# esquematico.net
KiCad netlist of a schematic drawn in EAGLE
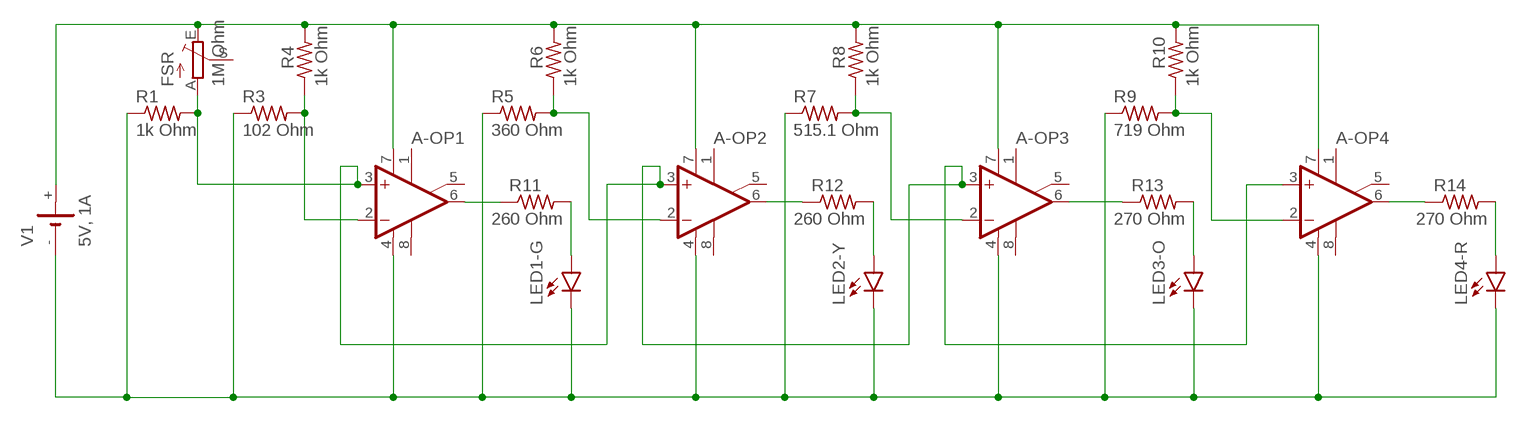
[diagram p0: schematic, sheet 1]

(export (version "E")
  (design (tool "Eeschema 10.0.6"))
  (components
    (comp (ref "A-OP1")
      (value "UA741P")
      (footprint "eagle-import:DIL08")
      (libsource (lib "eagle-import") (part "741PUA"))
    )
    (comp (ref "A-OP2")
      (value "UA741P")
      (footprint "eagle-import:DIL08")
      (libsource (lib "eagle-import") (part "741PUA"))
    )
    (comp (ref "A-OP3")
      (value "UA741P")
      (footprint "eagle-import:DIL08")
      (libsource (lib "eagle-import") (part "741PUA"))
    )
    (comp (ref "A-OP4")
      (value "UA741P")
      (footprint "eagle-import:DIL08")
      (libsource (lib "eagle-import") (part "741PUA"))
    )
    (comp (ref "FSR")
      (value "1M Ohm")
      (footprint "eagle-import:CIP20C-4MM")
      (libsource (lib "eagle-import") (part "TRIM_EU-CIP20C-4MM"))
    )
    (comp (ref "LED1-G")
      (value "TLLR4400")
      (footprint "eagle-import:LED3MM")
      (fields (field (name "MF") "VISHAY SEMICONDUCTOR"))
      (libsource (lib "eagle-import") (part "TLLR4400"))
    )
    (comp (ref "LED2-Y")
      (value "TLLR4400")
      (footprint "eagle-import:LED3MM")
      (fields (field (name "MF") "VISHAY SEMICONDUCTOR"))
      (libsource (lib "eagle-import") (part "TLLR4400"))
    )
    (comp (ref "LED3-O")
      (value "TLLR4400")
      (footprint "eagle-import:LED3MM")
      (fields (field (name "MF") "VISHAY SEMICONDUCTOR"))
      (libsource (lib "eagle-import") (part "TLLR4400"))
    )
    (comp (ref "LED4-R")
      (value "TLLR4400")
      (footprint "eagle-import:LED3MM")
      (fields (field (name "MF") "VISHAY SEMICONDUCTOR"))
      (libsource (lib "eagle-import") (part "TLLR4400"))
    )
    (comp (ref "R1")
      (value "1k Ohm")
      (footprint "eagle-import:0204_5")
      (libsource (lib "eagle-import") (part "R-US_0204/5"))
    )
    (comp (ref "R3")
      (value "102 Ohm")
      (footprint "eagle-import:0204_5")
      (libsource (lib "eagle-import") (part "R-US_0204/5"))
    )
    (comp (ref "R4")
      (value "1k Ohm")
      (footprint "eagle-import:0204_5")
      (libsource (lib "eagle-import") (part "R-US_0204/5"))
    )
    (comp (ref "R5")
      (value "360 Ohm")
      (footprint "eagle-import:0204_5")
      (libsource (lib "eagle-import") (part "R-US_0204/5"))
    )
    (comp (ref "R6")
      (value "1k Ohm")
      (footprint "eagle-import:0204_5")
      (libsource (lib "eagle-import") (part "R-US_0204/5"))
    )
    (comp (ref "R7")
      (value "515.1 Ohm")
      (footprint "eagle-import:0204_5")
      (libsource (lib "eagle-import") (part "R-US_0204/5"))
    )
    (comp (ref "R8")
      (value "1k Ohm")
      (footprint "eagle-import:0204_5")
      (libsource (lib "eagle-import") (part "R-US_0204/5"))
    )
    (comp (ref "R9")
      (value "719 Ohm")
      (footprint "eagle-import:0204_5")
      (libsource (lib "eagle-import") (part "R-US_0204/5"))
    )
    (comp (ref "R10")
      (value "1k Ohm")
      (footprint "eagle-import:0204_5")
      (libsource (lib "eagle-import") (part "R-US_0204/5"))
    )
    (comp (ref "R11")
      (value "260 Ohm")
      (footprint "eagle-import:0204_5")
      (libsource (lib "eagle-import") (part "R-US_0204/5"))
    )
    (comp (ref "R12")
      (value "260 Ohm")
      (footprint "eagle-import:0204_5")
      (libsource (lib "eagle-import") (part "R-US_0204/5"))
    )
    (comp (ref "R13")
      (value "270 Ohm")
      (footprint "eagle-import:0204_5")
      (libsource (lib "eagle-import") (part "R-US_0204/5"))
    )
    (comp (ref "R14")
      (value "270 Ohm")
      (footprint "eagle-import:0204_5")
      (libsource (lib "eagle-import") (part "R-US_0204/5"))
    )
    (comp (ref "V1")
      (value "5V, 1A")
      (footprint "eagle-import:CH291-1220LF")
      (libsource (lib "eagle-import") (part "CH291-1220LF"))
    )
  )
  (nets
    (net (code "1") (name "Net-(A-OP1-+IN)") (class "Default")
      (node (ref "A-OP1") (pin "3") (pinfunction "+IN_3") (pintype "input"))
      (node (ref "A-OP2") (pin "3") (pinfunction "+IN_3") (pintype "input"))
      (node (ref "A-OP3") (pin "3") (pinfunction "+IN_3") (pintype "input"))
      (node (ref "A-OP4") (pin "3") (pinfunction "+IN_3") (pintype "input"))
      (node (ref "FSR") (pin "A") (pinfunction "A_A") (pintype "passive"))
      (node (ref "R1") (pin "2") (pinfunction "2_2") (pintype "passive"))
    )
    (net (code "2") (name "Net-(A-OP1--IN)") (class "Default")
      (node (ref "A-OP1") (pin "2") (pinfunction "-IN_2") (pintype "input"))
      (node (ref "R3") (pin "2") (pinfunction "2_2") (pintype "passive"))
      (node (ref "R4") (pin "1") (pinfunction "1_1") (pintype "passive"))
    )
    (net (code "3") (name "Net-(A-OP1-OUT)") (class "Default")
      (node (ref "A-OP1") (pin "6") (pinfunction "OUT_6") (pintype "output"))
      (node (ref "R11") (pin "1") (pinfunction "1_1") (pintype "passive"))
    )
    (net (code "4") (name "Net-(A-OP1-V+)") (class "Default")
      (node (ref "A-OP1") (pin "7") (pinfunction "V+_7") (pintype "power_in"))
      (node (ref "A-OP2") (pin "7") (pinfunction "V+_7") (pintype "power_in"))
      (node (ref "A-OP3") (pin "7") (pinfunction "V+_7") (pintype "power_in"))
      (node (ref "A-OP4") (pin "7") (pinfunction "V+_7") (pintype "power_in"))
      (node (ref "FSR") (pin "E") (pinfunction "E_E") (pintype "passive"))
      (node (ref "R10") (pin "2") (pinfunction "2_2") (pintype "passive"))
      (node (ref "R4") (pin "2") (pinfunction "2_2") (pintype "passive"))
      (node (ref "R6") (pin "2") (pinfunction "2_2") (pintype "passive"))
      (node (ref "R8") (pin "2") (pinfunction "2_2") (pintype "passive"))
      (node (ref "V1") (pin "+") (pinfunction "+_+") (pintype "passive"))
    )
    (net (code "5") (name "Net-(A-OP1-V-)") (class "Default")
      (node (ref "A-OP1") (pin "4") (pinfunction "V-_4") (pintype "power_in"))
      (node (ref "A-OP2") (pin "4") (pinfunction "V-_4") (pintype "power_in"))
      (node (ref "A-OP3") (pin "4") (pinfunction "V-_4") (pintype "power_in"))
      (node (ref "A-OP4") (pin "4") (pinfunction "V-_4") (pintype "power_in"))
      (node (ref "LED1-G") (pin "K") (pinfunction "C_K") (pintype "passive"))
      (node (ref "LED2-Y") (pin "K") (pinfunction "C_K") (pintype "passive"))
      (node (ref "LED3-O") (pin "K") (pinfunction "C_K") (pintype "passive"))
      (node (ref "LED4-R") (pin "K") (pinfunction "C_K") (pintype "passive"))
      (node (ref "R1") (pin "1") (pinfunction "1_1") (pintype "passive"))
      (node (ref "R3") (pin "1") (pinfunction "1_1") (pintype "passive"))
      (node (ref "R5") (pin "1") (pinfunction "1_1") (pintype "passive"))
      (node (ref "R7") (pin "1") (pinfunction "1_1") (pintype "passive"))
      (node (ref "R9") (pin "1") (pinfunction "1_1") (pintype "passive"))
      (node (ref "V1") (pin "-") (pinfunction "-_-") (pintype "passive"))
    )
    (net (code "6") (name "Net-(A-OP2--IN)") (class "Default")
      (node (ref "A-OP2") (pin "2") (pinfunction "-IN_2") (pintype "input"))
      (node (ref "R5") (pin "2") (pinfunction "2_2") (pintype "passive"))
      (node (ref "R6") (pin "1") (pinfunction "1_1") (pintype "passive"))
    )
    (net (code "7") (name "Net-(A-OP2-OUT)") (class "Default")
      (node (ref "A-OP2") (pin "6") (pinfunction "OUT_6") (pintype "output"))
      (node (ref "R12") (pin "1") (pinfunction "1_1") (pintype "passive"))
    )
    (net (code "8") (name "Net-(A-OP3--IN)") (class "Default")
      (node (ref "A-OP3") (pin "2") (pinfunction "-IN_2") (pintype "input"))
      (node (ref "R7") (pin "2") (pinfunction "2_2") (pintype "passive"))
      (node (ref "R8") (pin "1") (pinfunction "1_1") (pintype "passive"))
    )
    (net (code "9") (name "Net-(A-OP3-OUT)") (class "Default")
      (node (ref "A-OP3") (pin "6") (pinfunction "OUT_6") (pintype "output"))
      (node (ref "R13") (pin "1") (pinfunction "1_1") (pintype "passive"))
    )
    (net (code "10") (name "Net-(A-OP4--IN)") (class "Default")
      (node (ref "A-OP4") (pin "2") (pinfunction "-IN_2") (pintype "input"))
      (node (ref "R10") (pin "1") (pinfunction "1_1") (pintype "passive"))
      (node (ref "R9") (pin "2") (pinfunction "2_2") (pintype "passive"))
    )
    (net (code "11") (name "Net-(A-OP4-OUT)") (class "Default")
      (node (ref "A-OP4") (pin "6") (pinfunction "OUT_6") (pintype "output"))
      (node (ref "R14") (pin "1") (pinfunction "1_1") (pintype "passive"))
    )
    (net (code "12") (name "Net-(LED1-G-PadA)") (class "Default")
      (node (ref "LED1-G") (pin "A") (pinfunction "A_A") (pintype "passive"))
      (node (ref "R11") (pin "2") (pinfunction "2_2") (pintype "passive"))
    )
    (net (code "13") (name "Net-(LED2-Y-PadA)") (class "Default")
      (node (ref "LED2-Y") (pin "A") (pinfunction "A_A") (pintype "passive"))
      (node (ref "R12") (pin "2") (pinfunction "2_2") (pintype "passive"))
    )
    (net (code "14") (name "Net-(LED3-O-PadA)") (class "Default")
      (node (ref "LED3-O") (pin "A") (pinfunction "A_A") (pintype "passive"))
      (node (ref "R13") (pin "2") (pinfunction "2_2") (pintype "passive"))
    )
    (net (code "15") (name "Net-(LED4-R-PadA)") (class "Default")
      (node (ref "LED4-R") (pin "A") (pinfunction "A_A") (pintype "passive"))
      (node (ref "R14") (pin "2") (pinfunction "2_2") (pintype "passive"))
    )
    (net (code "16") (name "unconnected-(A-OP1-ON1-Pad1)") (class "Default")
      (node (ref "A-OP1") (pin "1") (pinfunction "ON1_1") (pintype "passive"))
    )
    (net (code "17") (name "unconnected-(A-OP1-ON2-Pad5)") (class "Default")
      (node (ref "A-OP1") (pin "5") (pinfunction "ON2_5") (pintype "passive"))
    )
    (net (code "18") (name "unconnected-(A-OP1-OPT-Pad8)") (class "Default")
      (node (ref "A-OP1") (pin "8") (pinfunction "OPT_8") (pintype "passive"))
    )
    (net (code "19") (name "unconnected-(A-OP2-ON1-Pad1)") (class "Default")
      (node (ref "A-OP2") (pin "1") (pinfunction "ON1_1") (pintype "passive"))
    )
    (net (code "20") (name "unconnected-(A-OP2-ON2-Pad5)") (class "Default")
      (node (ref "A-OP2") (pin "5") (pinfunction "ON2_5") (pintype "passive"))
    )
    (net (code "21") (name "unconnected-(A-OP2-OPT-Pad8)") (class "Default")
      (node (ref "A-OP2") (pin "8") (pinfunction "OPT_8") (pintype "passive"))
    )
    (net (code "22") (name "unconnected-(A-OP3-ON1-Pad1)") (class "Default")
      (node (ref "A-OP3") (pin "1") (pinfunction "ON1_1") (pintype "passive"))
    )
    (net (code "23") (name "unconnected-(A-OP3-ON2-Pad5)") (class "Default")
      (node (ref "A-OP3") (pin "5") (pinfunction "ON2_5") (pintype "passive"))
    )
    (net (code "24") (name "unconnected-(A-OP3-OPT-Pad8)") (class "Default")
      (node (ref "A-OP3") (pin "8") (pinfunction "OPT_8") (pintype "passive"))
    )
    (net (code "25") (name "unconnected-(A-OP4-ON1-Pad1)") (class "Default")
      (node (ref "A-OP4") (pin "1") (pinfunction "ON1_1") (pintype "passive"))
    )
    (net (code "26") (name "unconnected-(A-OP4-ON2-Pad5)") (class "Default")
      (node (ref "A-OP4") (pin "5") (pinfunction "ON2_5") (pintype "passive"))
    )
    (net (code "27") (name "unconnected-(A-OP4-OPT-Pad8)") (class "Default")
      (node (ref "A-OP4") (pin "8") (pinfunction "OPT_8") (pintype "passive"))
    )
    (net (code "28") (name "unconnected-(FSR-PadS)") (class "Default")
      (node (ref "FSR") (pin "S") (pinfunction "S_S") (pintype "passive"))
    )
  )
)
